# DISPLAY.net
KiCad netlist of a schematic drawn in Altium Designer
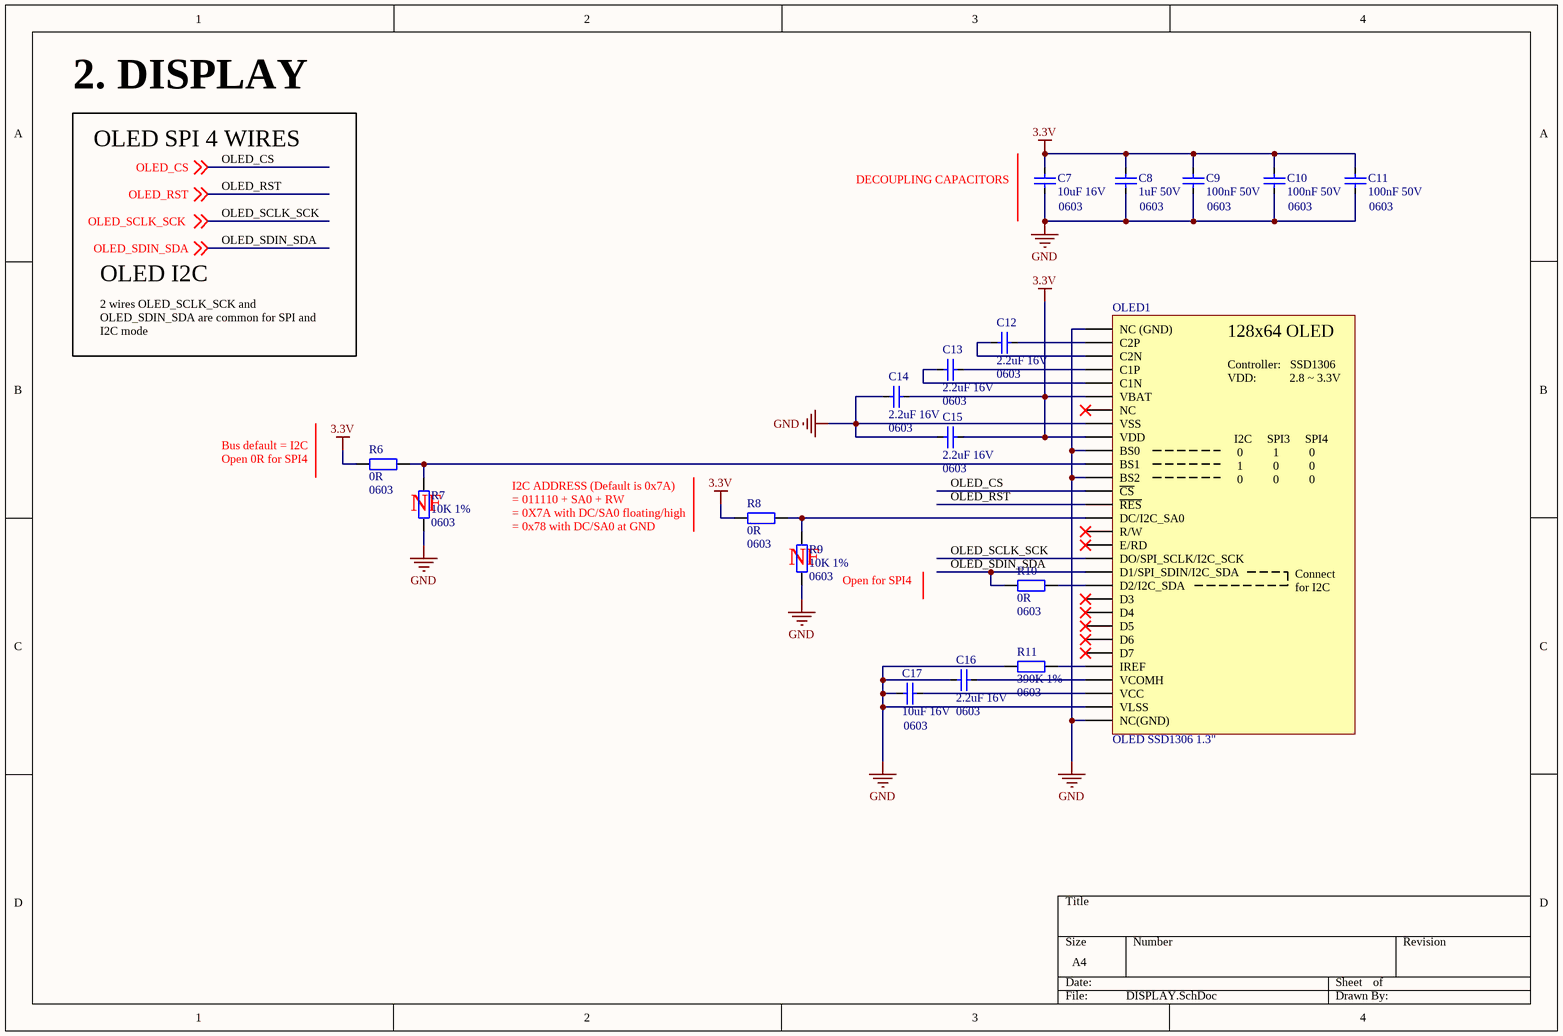
[diagram p0: DISPLAY.SchDoc]

(export (version "E")
  (design (tool "Eeschema 10.0.6"))
  (components
    (comp (ref "C7")
      (value "10uF 16V")
      (footprint "CAP_SMD_0603")
      (description "10 µF ±20% 16V Ceramic Capacitor X6S 0603 (1608 Metric)")
      (fields
        (field (name "MANUFACTURER") "Murata Electronics")
        (field (name "MANUFACTURE PART NUMBER") "GRM188C81C106MA73D")
        (field (name "SIZE") "0603")
      )
      (libsource (lib "Capacitors") (part "C0603_MLCC_10uF_16V"))
    )
    (comp (ref "C8")
      (value "1uF 50V")
      (footprint "CAP_SMD_0603")
      (description "1 µF ±10% 50V Ceramic Capacitor X5R 0603 (1608 Metric)")
      (fields
        (field (name "MANUFACTURER") "Samsung Electro-Mechanics")
        (field (name "MANUFACTURE PART NUMBER") "CL10A105KB8NNNC")
        (field (name "SIZE") "0603")
      )
      (libsource (lib "Capacitors") (part "C0603_MLCC_1uF_50V"))
    )
    (comp (ref "C9")
      (value "100nF 50V")
      (footprint "CAP_SMD_0603")
      (description "0.1 µF ±10% 50V Ceramic Capacitor X7R 0603 (1608 Metric)")
      (fields
        (field (name "MANUFACTURER") "Samsung Electro-Mechanics")
        (field (name "MANUFACTURE PART NUMBER") "CL10B104KB8NNNC")
        (field (name "SIZE") "0603")
      )
      (libsource (lib "Capacitors") (part "C0603_MLCC_100nF_50V"))
    )
    (comp (ref "C10")
      (value "100nF 50V")
      (footprint "CAP_SMD_0603")
      (description "0.1 µF ±10% 50V Ceramic Capacitor X7R 0603 (1608 Metric)")
      (fields
        (field (name "MANUFACTURER") "Samsung Electro-Mechanics")
        (field (name "MANUFACTURE PART NUMBER") "CL10B104KB8NNNC")
        (field (name "SIZE") "0603")
      )
      (libsource (lib "Capacitors") (part "C0603_MLCC_100nF_50V"))
    )
    (comp (ref "C11")
      (value "100nF 50V")
      (footprint "CAP_SMD_0603")
      (description "0.1 µF ±10% 50V Ceramic Capacitor X7R 0603 (1608 Metric)")
      (fields
        (field (name "MANUFACTURER") "Samsung Electro-Mechanics")
        (field (name "MANUFACTURE PART NUMBER") "CL10B104KB8NNNC")
        (field (name "SIZE") "0603")
      )
      (libsource (lib "Capacitors") (part "C0603_MLCC_100nF_50V"))
    )
    (comp (ref "C12")
      (value "2.2uF 16V")
      (footprint "CAP_SMD_0603")
      (description "2.2 µF ±10% 16V Ceramic Capacitor X5R 0603 (1608 Metric)")
      (fields
        (field (name "MANUFACTURER") "Samsung Electro-Mechanics")
        (field (name "MANUFACTURE PART NUMBER") "CL10A225KO8NNNC")
        (field (name "SIZE") "0603")
      )
      (libsource (lib "Capacitors") (part "C0603_MLCC_2.2uF_16V"))
    )
    (comp (ref "C13")
      (value "2.2uF 16V")
      (footprint "CAP_SMD_0603")
      (description "2.2 µF ±10% 16V Ceramic Capacitor X5R 0603 (1608 Metric)")
      (fields
        (field (name "MANUFACTURER") "Samsung Electro-Mechanics")
        (field (name "MANUFACTURE PART NUMBER") "CL10A225KO8NNNC")
        (field (name "SIZE") "0603")
      )
      (libsource (lib "Capacitors") (part "C0603_MLCC_2.2uF_16V"))
    )
    (comp (ref "C14")
      (value "2.2uF 16V")
      (footprint "CAP_SMD_0603")
      (description "2.2 µF ±10% 16V Ceramic Capacitor X5R 0603 (1608 Metric)")
      (fields
        (field (name "MANUFACTURER") "Samsung Electro-Mechanics")
        (field (name "MANUFACTURE PART NUMBER") "CL10A225KO8NNNC")
        (field (name "SIZE") "0603")
      )
      (libsource (lib "Capacitors") (part "C0603_MLCC_2.2uF_16V"))
    )
    (comp (ref "C15")
      (value "2.2uF 16V")
      (footprint "CAP_SMD_0603")
      (description "2.2 µF ±10% 16V Ceramic Capacitor X5R 0603 (1608 Metric)")
      (fields
        (field (name "MANUFACTURER") "Samsung Electro-Mechanics")
        (field (name "MANUFACTURE PART NUMBER") "CL10A225KO8NNNC")
        (field (name "SIZE") "0603")
      )
      (libsource (lib "Capacitors") (part "C0603_MLCC_2.2uF_16V"))
    )
    (comp (ref "C16")
      (value "2.2uF 16V")
      (footprint "CAP_SMD_0603")
      (description "2.2 µF ±10% 16V Ceramic Capacitor X5R 0603 (1608 Metric)")
      (fields
        (field (name "MANUFACTURER") "Samsung Electro-Mechanics")
        (field (name "MANUFACTURE PART NUMBER") "CL10A225KO8NNNC")
        (field (name "SIZE") "0603")
      )
      (libsource (lib "Capacitors") (part "C0603_MLCC_2.2uF_16V"))
    )
    (comp (ref "C17")
      (value "10uF 16V")
      (footprint "CAP_SMD_0603")
      (description "10 µF ±20% 16V Ceramic Capacitor X6S 0603 (1608 Metric)")
      (fields
        (field (name "MANUFACTURER") "Murata Electronics")
        (field (name "MANUFACTURE PART NUMBER") "GRM188C81C106MA73D")
        (field (name "SIZE") "0603")
      )
      (libsource (lib "Capacitors") (part "C0603_MLCC_10uF_16V"))
    )
    (comp (ref "OLED1")
      (value "OLED SSD1306 1.3\"")
      (footprint "OLED 1.3")
      (description "SSD1306 1.3 - Organic Light Emitting Diode Display Screen ROHS")
      (fields
        (field (name "MANUFACTURER") "UG(Univision Semicon)")
        (field (name "MANUFACTURE PART NUMBER") "UG-2864KSWLG01")
      )
      (libsource (lib "TFT_LCD") (part "1.3{dblquote}_SSD1306_OLED"))
    )
    (comp (ref "R6")
      (value "0R")
      (footprint "RES_SMD_0603")
      (description "0 Ohms Jumper Chip Resistor 0603 (1608 Metric) Automotive AEC-Q200 Thick Film")
      (fields
        (field (name "MANUFACTURER") "Stackpole Electronics Inc")
        (field (name "MANUFACTURE PART NUMBER") "RMCF0603ZT0R00")
        (field (name "SIZE") "0603")
      )
      (libsource (lib "Resistors") (part "R0603_0R"))
    )
    (comp (ref "R7")
      (value "10K 1%")
      (footprint "RES_SMD_0603")
      (description "10 kOhms ±1% 0.1W, 1/10W Chip Resistor 0603 (1608 Metric) Moisture Resistant Thick Film")
      (fields
        (field (name "MANUFACTURER") "YAGEO")
        (field (name "MANUFACTURE PART NUMBER") "RC0603FR-0710KL")
        (field (name "SIZE") "0603")
      )
      (libsource (lib "Resistors") (part "R0603_10K"))
    )
    (comp (ref "R8")
      (value "0R")
      (footprint "RES_SMD_0603")
      (description "0 Ohms Jumper Chip Resistor 0603 (1608 Metric) Automotive AEC-Q200 Thick Film")
      (fields
        (field (name "MANUFACTURER") "Stackpole Electronics Inc")
        (field (name "MANUFACTURE PART NUMBER") "RMCF0603ZT0R00")
        (field (name "SIZE") "0603")
      )
      (libsource (lib "Resistors") (part "R0603_0R"))
    )
    (comp (ref "R9")
      (value "10K 1%")
      (footprint "RES_SMD_0603")
      (description "10 kOhms ±1% 0.1W, 1/10W Chip Resistor 0603 (1608 Metric) Moisture Resistant Thick Film")
      (fields
        (field (name "MANUFACTURER") "YAGEO")
        (field (name "MANUFACTURE PART NUMBER") "RC0603FR-0710KL")
        (field (name "SIZE") "0603")
      )
      (libsource (lib "Resistors") (part "R0603_10K"))
    )
    (comp (ref "R10")
      (value "0R")
      (footprint "RES_SMD_0603")
      (description "0 Ohms Jumper Chip Resistor 0603 (1608 Metric) Automotive AEC-Q200 Thick Film")
      (fields
        (field (name "MANUFACTURER") "Stackpole Electronics Inc")
        (field (name "MANUFACTURE PART NUMBER") "RMCF0603ZT0R00")
        (field (name "SIZE") "0603")
      )
      (libsource (lib "Resistors") (part "R0603_0R"))
    )
    (comp (ref "R11")
      (value "390K 1%")
      (footprint "RES_SMD_0603")
      (description "390 kOhms ±1% 0.1W, 1/10W Chip Resistor 0603 (1608 Metric) Moisture Resistant Thick Film")
      (fields
        (field (name "MANUFACTURER") "YAGEO")
        (field (name "MANUFACTURE PART NUMBER") "RC0603FR-07390KL")
        (field (name "SIZE") "0603")
      )
      (libsource (lib "Resistors") (part "R0603_390K"))
    )
  )
  (nets
    (net (code "1") (name "3.3V") (class "Default")
      (node (ref "C10") (pin "2") (pinfunction "2_2") (pintype "passive"))
      (node (ref "C11") (pin "2") (pinfunction "2_2") (pintype "passive"))
      (node (ref "C14") (pin "2") (pinfunction "2_2") (pintype "passive"))
      (node (ref "C15") (pin "2") (pinfunction "2_2") (pintype "passive"))
      (node (ref "C7") (pin "2") (pinfunction "2_2") (pintype "passive"))
      (node (ref "C8") (pin "2") (pinfunction "2_2") (pintype "passive"))
      (node (ref "C9") (pin "2") (pinfunction "2_2") (pintype "passive"))
      (node (ref "OLED1") (pin "A6") (pinfunction "VBAT_A6") (pintype "passive"))
      (node (ref "OLED1") (pin "A9") (pinfunction "VDD_A9") (pintype "passive"))
      (node (ref "R6") (pin "1") (pinfunction "1_1") (pintype "passive"))
      (node (ref "R8") (pin "1") (pinfunction "1_1") (pintype "passive"))
    )
    (net (code "2") (name "GND") (class "Default")
      (node (ref "C10") (pin "1") (pinfunction "1_1") (pintype "passive"))
      (node (ref "C11") (pin "1") (pinfunction "1_1") (pintype "passive"))
      (node (ref "C14") (pin "1") (pinfunction "1_1") (pintype "passive"))
      (node (ref "C15") (pin "1") (pinfunction "1_1") (pintype "passive"))
      (node (ref "C16") (pin "2") (pinfunction "2_2") (pintype "passive"))
      (node (ref "C17") (pin "1") (pinfunction "1_1") (pintype "passive"))
      (node (ref "C7") (pin "1") (pinfunction "1_1") (pintype "passive"))
      (node (ref "C8") (pin "1") (pinfunction "1_1") (pintype "passive"))
      (node (ref "C9") (pin "1") (pinfunction "1_1") (pintype "passive"))
      (node (ref "OLED1") (pin "A1") (pinfunction "NC_(GND)_A1") (pintype "passive"))
      (node (ref "OLED1") (pin "A10") (pinfunction "BS0_A10") (pintype "passive"))
      (node (ref "OLED1") (pin "A12") (pinfunction "BS2_A12") (pintype "passive"))
      (node (ref "OLED1") (pin "A29") (pinfunction "VLSS_A29") (pintype "passive"))
      (node (ref "OLED1") (pin "A30") (pinfunction "NC(GND)_A30") (pintype "passive"))
      (node (ref "OLED1") (pin "A8") (pinfunction "VSS_A8") (pintype "passive"))
      (node (ref "R11") (pin "1") (pinfunction "1_1") (pintype "passive"))
      (node (ref "R7") (pin "1") (pinfunction "1_1") (pintype "passive"))
      (node (ref "R9") (pin "1") (pinfunction "1_1") (pintype "passive"))
    )
    (net (code "3") (name "Net-(OLED1-BS1)") (class "Default")
      (node (ref "OLED1") (pin "A11") (pinfunction "BS1_A11") (pintype "passive"))
      (node (ref "R6") (pin "2") (pinfunction "2_2") (pintype "passive"))
      (node (ref "R7") (pin "2") (pinfunction "2_2") (pintype "passive"))
    )
    (net (code "4") (name "Net-(OLED1-C1N)") (class "Default")
      (node (ref "C13") (pin "1") (pinfunction "1_1") (pintype "passive"))
      (node (ref "OLED1") (pin "A5") (pinfunction "C1N_A5") (pintype "passive"))
    )
    (net (code "5") (name "Net-(OLED1-C1P)") (class "Default")
      (node (ref "C13") (pin "2") (pinfunction "2_2") (pintype "passive"))
      (node (ref "OLED1") (pin "A4") (pinfunction "C1P_A4") (pintype "passive"))
    )
    (net (code "6") (name "Net-(OLED1-C2N)") (class "Default")
      (node (ref "C12") (pin "2") (pinfunction "2_2") (pintype "passive"))
      (node (ref "OLED1") (pin "A3") (pinfunction "C2N_A3") (pintype "passive"))
    )
    (net (code "7") (name "Net-(OLED1-C2P)") (class "Default")
      (node (ref "C12") (pin "1") (pinfunction "1_1") (pintype "passive"))
      (node (ref "OLED1") (pin "A2") (pinfunction "C2P_A2") (pintype "passive"))
    )
    (net (code "8") (name "Net-(OLED1-D2{slash}I2C_SDA)") (class "Default")
      (node (ref "OLED1") (pin "A20") (pinfunction "D2/I2C_SDA_A20") (pintype "passive"))
      (node (ref "R10") (pin "2") (pinfunction "2_2") (pintype "passive"))
    )
    (net (code "9") (name "Net-(OLED1-DC{slash}I2C_SA0)") (class "Default")
      (node (ref "OLED1") (pin "A15") (pinfunction "DC/I2C_SA0_A15") (pintype "passive"))
      (node (ref "R8") (pin "2") (pinfunction "2_2") (pintype "passive"))
      (node (ref "R9") (pin "2") (pinfunction "2_2") (pintype "passive"))
    )
    (net (code "10") (name "Net-(OLED1-IREF)") (class "Default")
      (node (ref "OLED1") (pin "A26") (pinfunction "IREF_A26") (pintype "passive"))
      (node (ref "R11") (pin "2") (pinfunction "2_2") (pintype "passive"))
    )
    (net (code "11") (name "Net-(OLED1-VCC)") (class "Default")
      (node (ref "C17") (pin "2") (pinfunction "2_2") (pintype "passive"))
      (node (ref "OLED1") (pin "A28") (pinfunction "VCC_A28") (pintype "passive"))
    )
    (net (code "12") (name "Net-(OLED1-VCOMH)") (class "Default")
      (node (ref "C16") (pin "1") (pinfunction "1_1") (pintype "passive"))
      (node (ref "OLED1") (pin "A27") (pinfunction "VCOMH_A27") (pintype "passive"))
    )
    (net (code "13") (name "OLED_CS") (class "Default")
      (node (ref "OLED1") (pin "A13") (pinfunction "~{CS}_A13") (pintype "passive"))
    )
    (net (code "14") (name "OLED_RST") (class "Default")
      (node (ref "OLED1") (pin "A14") (pinfunction "~{RES}_A14") (pintype "passive"))
    )
    (net (code "15") (name "OLED_SCLK_SCK") (class "Default")
      (node (ref "OLED1") (pin "A18") (pinfunction "DO/SPI_SCLK/I2C_SCK_A18") (pintype "passive"))
    )
    (net (code "16") (name "OLED_SDIN_SDA") (class "Default")
      (node (ref "OLED1") (pin "A19") (pinfunction "D1/SPI_SDIN/I2C_SDA_A19") (pintype "passive"))
      (node (ref "R10") (pin "1") (pinfunction "1_1") (pintype "passive"))
    )
    (net (code "17") (name "unconnected-(OLED1-D3-PadA21)") (class "Default")
      (node (ref "OLED1") (pin "A21") (pinfunction "D3_A21") (pintype "passive+no_connect"))
    )
    (net (code "18") (name "unconnected-(OLED1-D4-PadA22)") (class "Default")
      (node (ref "OLED1") (pin "A22") (pinfunction "D4_A22") (pintype "passive+no_connect"))
    )
    (net (code "19") (name "unconnected-(OLED1-D5-PadA23)") (class "Default")
      (node (ref "OLED1") (pin "A23") (pinfunction "D5_A23") (pintype "passive+no_connect"))
    )
    (net (code "20") (name "unconnected-(OLED1-D6-PadA24)") (class "Default")
      (node (ref "OLED1") (pin "A24") (pinfunction "D6_A24") (pintype "passive+no_connect"))
    )
    (net (code "21") (name "unconnected-(OLED1-D7-PadA25)") (class "Default")
      (node (ref "OLED1") (pin "A25") (pinfunction "D7_A25") (pintype "passive+no_connect"))
    )
    (net (code "22") (name "unconnected-(OLED1-E{slash}RD-PadA17)") (class "Default")
      (node (ref "OLED1") (pin "A17") (pinfunction "E/RD_A17") (pintype "passive+no_connect"))
    )
    (net (code "23") (name "unconnected-(OLED1-NC-PadA7)") (class "Default")
      (node (ref "OLED1") (pin "A7") (pinfunction "NC_A7") (pintype "passive+no_connect"))
    )
    (net (code "24") (name "unconnected-(OLED1-R{slash}W-PadA16)") (class "Default")
      (node (ref "OLED1") (pin "A16") (pinfunction "R/W_A16") (pintype "passive+no_connect"))
    )
  )
)
